# DetectorOptode.net
KiCad netlist of a schematic drawn in Altium Designer
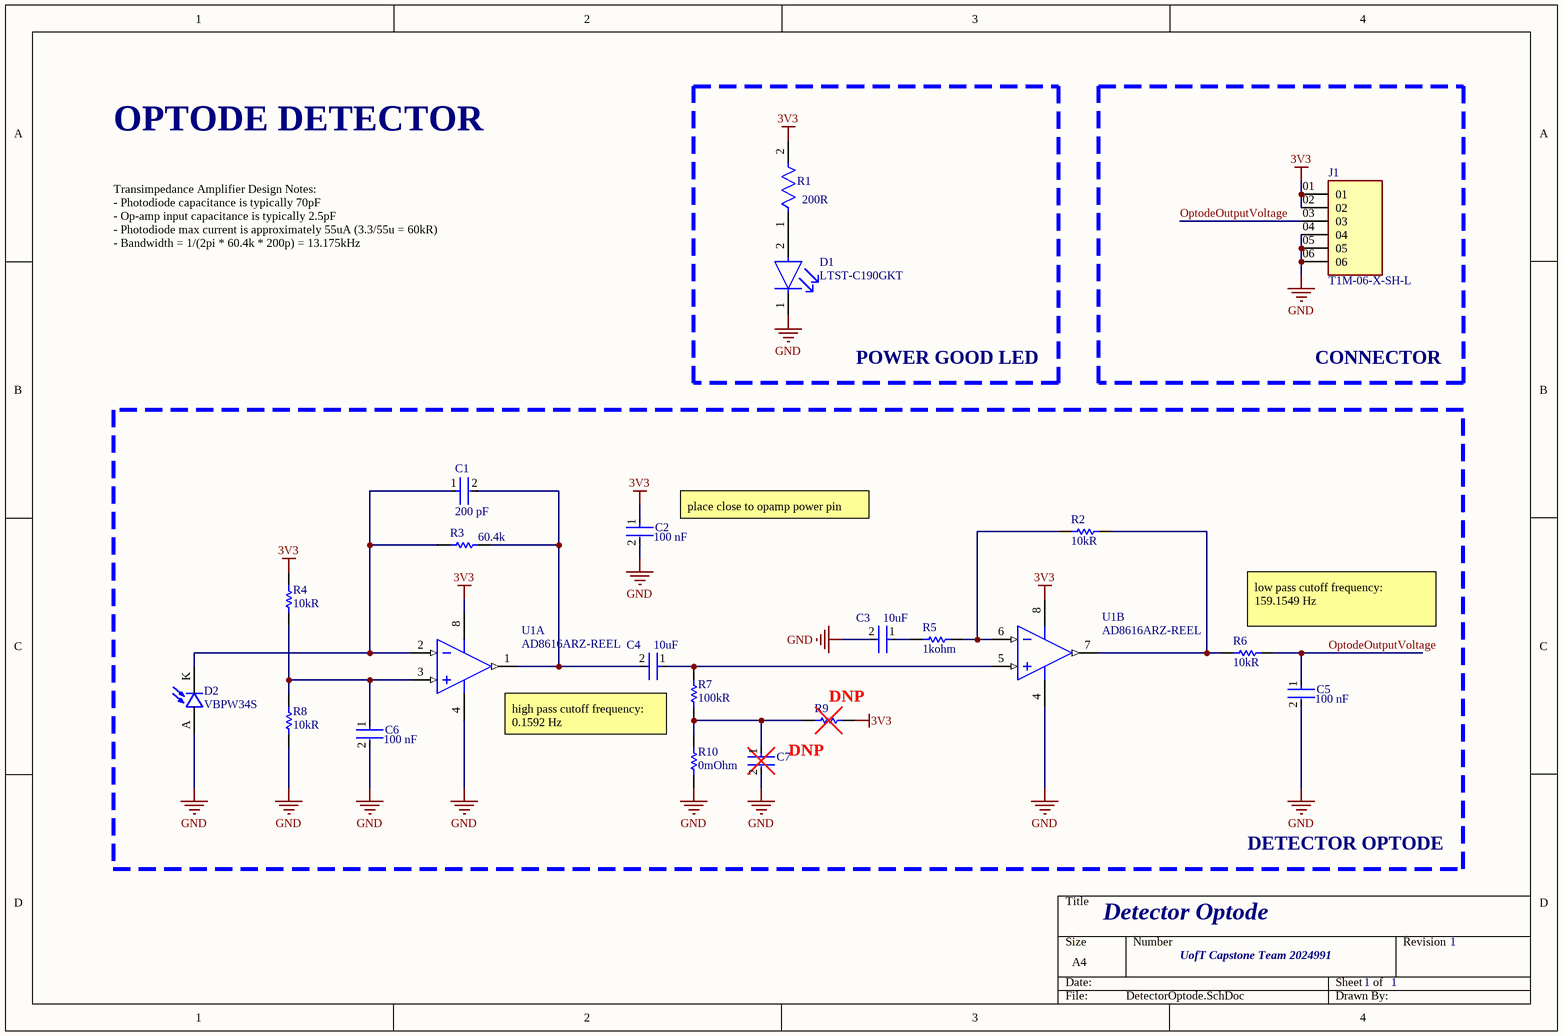
[diagram p0: DetectorOptode.SchDoc]

(export (version "E")
  (design (tool "Eeschema 10.0.6"))
  (components
    (comp (ref "C1")
      (value "C0603C201J5GACTU")
      (footprint "FP-C0603C-CF-MFG")
      (description "CAP CER 200PF 50V 5% NP0 0603")
      (fields
        (field (name "CAPACITANCE") "200 pF")
        (field (name "MANUFACTURER") "KEMET")
        (field (name "OCTOPART") "https://octopart.com/c0603c201j5gactu-kemet-9143917")
      )
      (libsource (lib "Altium Content Vault") (part "b4654b650e69147ec39a6b967a45e02"))
    )
    (comp (ref "C2")
      (value "CC0603KRX7R7BB104")
      (footprint "FP-CC0603-DA-MFG")
      (description "CAP CER 0.1UF 16V X7R 0603")
      (fields
        (field (name "OCTOPART") "https://octopart.com/cc0603krx7r7bb104-yageo-192941")
        (field (name "TOLERANCE") "0.1")
        (field (name "CAPACITANCE") "100 nF")
      )
      (libsource (lib "Altium Content Vault") (part "11868f565c42a9108669ba33697ecf6"))
    )
    (comp (ref "C3")
      (value "GRM188R60J106ME47D")
      (footprint "FP-GRM188-0_1-e0_2_0_55-IPC_C")
      (description "Chip Multilayer Ceramic Capacitors for General Purpose, 0603, 10uF, X5R, 15%, 20%, 6.3V")
      (fields
        (field (name "CAPACITANCE") "10uF")
        (field (name "VOLTAGE") "6.3V")
        (field (name "TOLERANCE") "20%")
      )
      (libsource (lib "Altium Content Vault") (part "02cd4be3c70576c341d710602a673aa"))
    )
    (comp (ref "C4")
      (value "GRM188R60J106ME47D")
      (footprint "FP-GRM188-0_1-e0_2_0_55-IPC_C")
      (description "Chip Multilayer Ceramic Capacitors for General Purpose, 0603, 10uF, X5R, 15%, 20%, 6.3V")
      (fields
        (field (name "CAPACITANCE") "10uF")
        (field (name "VOLTAGE") "6.3V")
        (field (name "TOLERANCE") "20%")
      )
      (libsource (lib "Altium Content Vault") (part "02cd4be3c70576c341d710602a673aa"))
    )
    (comp (ref "C5")
      (value "CC0603KRX7R7BB104")
      (footprint "FP-CC0603-DA-MFG")
      (description "CAP CER 0.1UF 16V X7R 0603")
      (fields
        (field (name "OCTOPART") "https://octopart.com/cc0603krx7r7bb104-yageo-192941")
        (field (name "TOLERANCE") "0.1")
        (field (name "CAPACITANCE") "100 nF")
      )
      (libsource (lib "Altium Content Vault") (part "11868f565c42a9108669ba33697ecf6"))
    )
    (comp (ref "C6")
      (value "CC0603KRX7R7BB104")
      (footprint "FP-CC0603-DA-MFG")
      (description "CAP CER 0.1UF 16V X7R 0603")
      (fields
        (field (name "OCTOPART") "https://octopart.com/cc0603krx7r7bb104-yageo-192941")
        (field (name "TOLERANCE") "0.1")
        (field (name "CAPACITANCE") "100 nF")
      )
      (libsource (lib "Altium Content Vault") (part "11868f565c42a9108669ba33697ecf6"))
    )
    (comp (ref "C7")
      (value "CC0603KRX7R7BB104")
      (footprint "FP-CC0603-DA-MFG")
      (description "CAP CER 0.1UF 16V X7R 0603")
      (fields
        (field (name "OCTOPART") "https://octopart.com/cc0603krx7r7bb104-yageo-192941")
        (field (name "TOLERANCE") "0.1")
      )
      (libsource (lib "Altium Content Vault") (part "11868f565c42a9108669ba33697ecf6"))
    )
    (comp (ref "D1")
      (value "LTST-C190GKT")
      (footprint "FP-LTST-C190GKT-MFG")
      (description "LED GREEN CLEAR CHIP SMD")
      (fields (field (name "VOLTAGE") "2V"))
      (libsource (lib "Altium Content Vault") (part "8706943c75ba83719d021d2fdc84c58"))
    )
    (comp (ref "D2")
      (value "VBPW34S")
      (footprint "PcbLib1:XDCR_VBPW34S")
      (description "Photodiode 940nm 100ns 130Â° 2-SMD, Gull Wing")
      (fields (field (name "MF") "Vishay"))
      (libsource (lib "SourceOptode") (part "VBPW34S"))
    )
    (comp (ref "J1")
      (value "T1M-06-X-SH-L")
      (footprint "SAMTEC_T1M-06-X-SH-L")
      (description "Connector Header Surface Mount, Right Angle 6 position 0.039\" (1.00mm)")
      (fields (field (name "MF") "Samtec"))
      (libsource (lib "Schlib1") (part "T1M-06-X-SH-L"))
    )
    (comp (ref "R1")
      (value "CRCW0603200RFKEA")
      (footprint "FP-CRCW0603-e3-MFG")
      (description "RES Thick Film, 200Ω, 1%, 0.1W, 100ppm/°C, 0603")
      (fields (field (name "TOLERANCE") "1%") (field (name "RESISTANCE") "200R"))
      (libsource (lib "Altium Content Vault") (part "1029c3af85768c4190bb7ad29bc67b5"))
    )
    (comp (ref "R2")
      (value "CRCW060310K0FKEA")
      (footprint "RESC1609X50X30NL8T20")
      (description "Chip Resistor, 10 KOhm, +/- 1%, 100 mW, -55 to 155 degC, 0603 (1608 Metric), RoHS, Tape and Reel")
      (fields (field (name "MANUFACTURER") "Vishay Semiconductor") (field (name "RESISTANCE") "10kR"))
      (libsource (lib "Altium Content Vault") (part "RES-2"))
    )
    (comp (ref "R3")
      (value "RC0603FR-0760K4L")
      (footprint "RESC1608X55X25ML10T15")
      (fields (field (name "MANUFACTURER") "Yageo") (field (name "RESISTANCE") "60.4k"))
      (libsource (lib "Altium Content Vault") (part "RES"))
    )
    (comp (ref "R4")
      (value "CRCW060310K0FKEA")
      (footprint "RESC1609X50X30NL8T20")
      (description "Chip Resistor, 10 KOhm, +/- 1%, 100 mW, -55 to 155 degC, 0603 (1608 Metric), RoHS, Tape and Reel")
      (fields (field (name "MANUFACTURER") "Vishay Semiconductor") (field (name "RESISTANCE") "10kR"))
      (libsource (lib "Altium Content Vault") (part "RES-2"))
    )
    (comp (ref "R5")
      (value "RC0603JR-071KL")
      (footprint "RESC1608X55X25ML10T15")
      (description "Chip Resistor, 1 KOhm, +/- 5%, 0.063 W, -55 to 155 degC, 0603 (1608 Metric), RoHS, Tape and Reel")
      (fields (field (name "RESISTANCE") "1kohm") (field (name "MANUFACTURER") "Yageo"))
      (libsource (lib "Altium Content Vault") (part "RES-2"))
    )
    (comp (ref "R6")
      (value "CRCW060310K0FKEA")
      (footprint "RESC1609X50X30NL8T20")
      (description "Chip Resistor, 10 KOhm, +/- 1%, 100 mW, -55 to 155 degC, 0603 (1608 Metric), RoHS, Tape and Reel")
      (fields (field (name "MANUFACTURER") "Vishay Semiconductor") (field (name "RESISTANCE") "10kR"))
      (libsource (lib "Altium Content Vault") (part "RES-2"))
    )
    (comp (ref "R7")
      (value "ERJ-3EKF1003V")
      (footprint "RESC1608X55X30ML15T15")
      (fields (field (name "MANUFACTURER") "Panasonic") (field (name "RESISTANCE") "100kR"))
      (libsource (lib "Altium Content Vault") (part "RES"))
    )
    (comp (ref "R8")
      (value "CRCW060310K0FKEA")
      (footprint "RESC1609X50X30NL8T20")
      (description "Chip Resistor, 10 KOhm, +/- 1%, 100 mW, -55 to 155 degC, 0603 (1608 Metric), RoHS, Tape and Reel")
      (fields (field (name "MANUFACTURER") "Vishay Semiconductor") (field (name "RESISTANCE") "10kR"))
      (libsource (lib "Altium Content Vault") (part "RES-2"))
    )
    (comp (ref "R9")
      (value "CRCW060310K0FKEA")
      (footprint "RESC1609X50X30NL8T20")
      (description "Chip Resistor, 10 KOhm, +/- 1%, 100 mW, -55 to 155 degC, 0603 (1608 Metric), RoHS, Tape and Reel")
      (fields (field (name "MANUFACTURER") "Vishay Semiconductor"))
      (libsource (lib "Altium Content Vault") (part "RES-2"))
    )
    (comp (ref "R10")
      (value "RC0603JR-070RL")
      (footprint "RESC1608X55X25ML10T15")
      (description "Chip Resistor, 0 Ohm, +/- 5%, 0.1 W, -55 to 155 degC, 0603 (1608 Metric), RoHS, Tape and Reel")
      (fields
        (field (name "TOLERANCE") "5%")
        (field (name "RESISTANCE") "0mOhm")
        (field (name "MANUFACTURER") "Yageo")
      )
      (libsource (lib "Altium Content Vault") (part "RES-2"))
    )
    (comp (ref "U1")
      (value "AD8616ARZ-REEL")
      (footprint "ADI-R-8_N")
      (fields (field (name "MANUFACTURER") "Analog Devices") (field (name "GENERIC PART NUMBER") "AD8616"))
      (libsource (lib "Altium Content Vault") (part "ADI-OP29X-R-8"))
    )
  )
  (nets
    (net (code "1") (name "/OptodeOutputVoltage") (class "Default")
      (node (ref "C5") (pin "1") (pinfunction "1_1") (pintype "passive"))
      (node (ref "J1") (pin "03") (pinfunction "03_03") (pintype "passive"))
      (node (ref "R6") (pin "1") (pinfunction "1_1") (pintype "passive"))
    )
    (net (code "2") (name "3V3") (class "Default")
      (node (ref "C2") (pin "1") (pinfunction "1_1") (pintype "passive"))
      (node (ref "J1") (pin "01") (pinfunction "01_01") (pintype "passive"))
      (node (ref "J1") (pin "02") (pinfunction "02_02") (pintype "passive"))
      (node (ref "R1") (pin "2") (pinfunction "2_2") (pintype "passive"))
      (node (ref "R4") (pin "2") (pinfunction "2_2") (pintype "passive"))
      (node (ref "R9") (pin "2") (pinfunction "2_2") (pintype "passive"))
      (node (ref "U1") (pin "8") (pinfunction "+V_8") (pintype "power_in"))
    )
    (net (code "3") (name "GND") (class "Default")
      (node (ref "C2") (pin "2") (pinfunction "2_2") (pintype "passive"))
      (node (ref "C3") (pin "2") (pinfunction "2_2") (pintype "passive"))
      (node (ref "C5") (pin "2") (pinfunction "2_2") (pintype "passive"))
      (node (ref "C6") (pin "2") (pinfunction "2_2") (pintype "passive"))
      (node (ref "C7") (pin "2") (pinfunction "2_2") (pintype "passive"))
      (node (ref "D1") (pin "1") (pinfunction "C_1") (pintype "passive"))
      (node (ref "D2") (pin "A") (pinfunction "A_A") (pintype "passive"))
      (node (ref "J1") (pin "04") (pinfunction "04_04") (pintype "passive"))
      (node (ref "J1") (pin "05") (pinfunction "05_05") (pintype "passive"))
      (node (ref "J1") (pin "06") (pinfunction "06_06") (pintype "passive"))
      (node (ref "R10") (pin "1") (pinfunction "1_1") (pintype "passive"))
      (node (ref "R8") (pin "1") (pinfunction "1_1") (pintype "passive"))
      (node (ref "U1") (pin "4") (pinfunction "-V_4") (pintype "power_in"))
    )
    (net (code "4") (name "Net-(C3-Pad1)") (class "Default")
      (node (ref "C3") (pin "1") (pinfunction "1_1") (pintype "passive"))
      (node (ref "R5") (pin "1") (pinfunction "1_1") (pintype "passive"))
    )
    (net (code "5") (name "Net-(C7-Pad1)") (class "Default")
      (node (ref "C7") (pin "1") (pinfunction "1_1") (pintype "passive"))
      (node (ref "R10") (pin "2") (pinfunction "2_2") (pintype "passive"))
      (node (ref "R7") (pin "1") (pinfunction "1_1") (pintype "passive"))
      (node (ref "R9") (pin "1") (pinfunction "1_1") (pintype "passive"))
    )
    (net (code "6") (name "Net-(D1-A)") (class "Default")
      (node (ref "D1") (pin "2") (pinfunction "A_2") (pintype "passive"))
      (node (ref "R1") (pin "1") (pinfunction "1_1") (pintype "passive"))
    )
    (net (code "7") (name "Net-(D2-C)") (class "Default")
      (node (ref "C1") (pin "1") (pinfunction "1_1") (pintype "passive"))
      (node (ref "D2") (pin "K") (pinfunction "C_K") (pintype "passive"))
      (node (ref "R3") (pin "1") (pinfunction "1_1") (pintype "passive"))
      (node (ref "U1") (pin "2") (pinfunction "-IN_A_2") (pintype "input"))
    )
    (net (code "8") (name "Net-(U1A-+IN_A)") (class "Default")
      (node (ref "C6") (pin "1") (pinfunction "1_1") (pintype "passive"))
      (node (ref "R4") (pin "1") (pinfunction "1_1") (pintype "passive"))
      (node (ref "R8") (pin "2") (pinfunction "2_2") (pintype "passive"))
      (node (ref "U1") (pin "3") (pinfunction "+IN_A_3") (pintype "input"))
    )
    (net (code "9") (name "Net-(U1A-OUT_A)") (class "Default")
      (node (ref "C1") (pin "2") (pinfunction "2_2") (pintype "passive"))
      (node (ref "C4") (pin "2") (pinfunction "2_2") (pintype "passive"))
      (node (ref "R3") (pin "2") (pinfunction "2_2") (pintype "passive"))
      (node (ref "U1") (pin "1") (pinfunction "OUT_A_1") (pintype "output"))
    )
    (net (code "10") (name "Net-(U1B-+IN_B)") (class "Default")
      (node (ref "C4") (pin "1") (pinfunction "1_1") (pintype "passive"))
      (node (ref "R7") (pin "2") (pinfunction "2_2") (pintype "passive"))
      (node (ref "U1") (pin "5") (pinfunction "+IN_B_5") (pintype "input"))
    )
    (net (code "11") (name "Net-(U1B--IN_B)") (class "Default")
      (node (ref "R2") (pin "2") (pinfunction "2_2") (pintype "passive"))
      (node (ref "R5") (pin "2") (pinfunction "2_2") (pintype "passive"))
      (node (ref "U1") (pin "6") (pinfunction "-IN_B_6") (pintype "input"))
    )
    (net (code "12") (name "Net-(U1B-OUT_B)") (class "Default")
      (node (ref "R2") (pin "1") (pinfunction "1_1") (pintype "passive"))
      (node (ref "R6") (pin "2") (pinfunction "2_2") (pintype "passive"))
      (node (ref "U1") (pin "7") (pinfunction "OUT_B_7") (pintype "output"))
    )
  )
)
